# DM1098LUXD-LITE_Power_Supply.net
KiCad netlist of a schematic drawn in Altium Designer
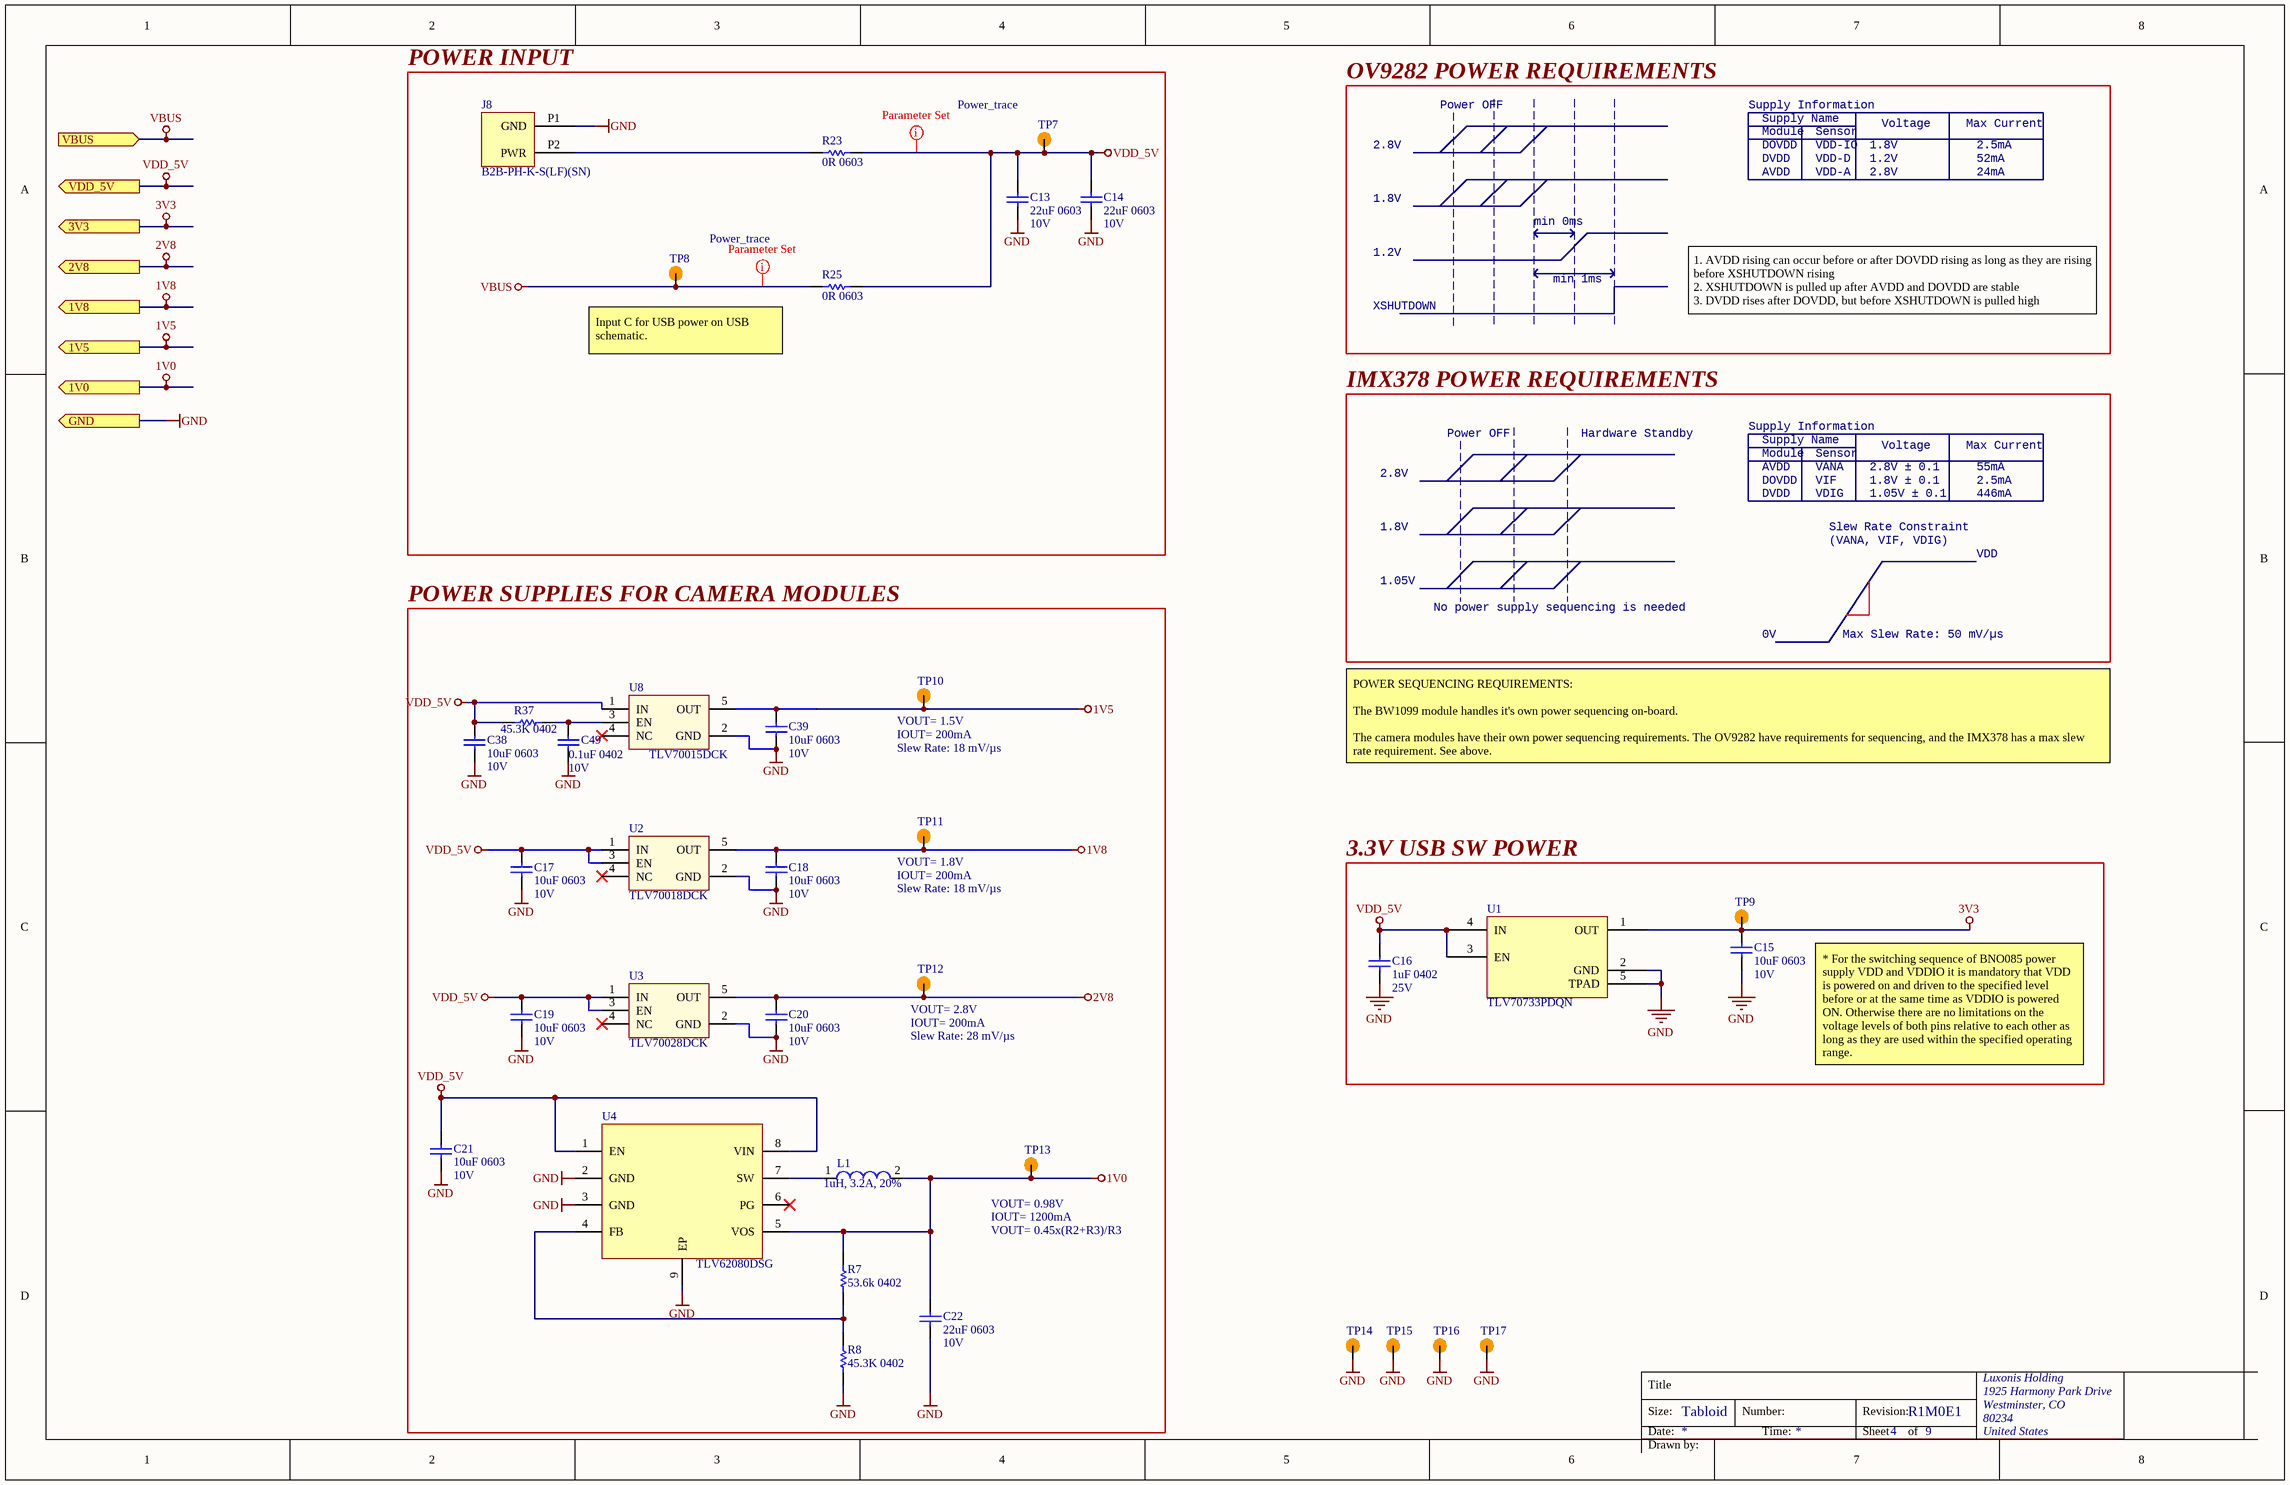
[diagram p0: DM1098LUXD-LITE_Power_Supply.SchDoc]

(export (version "E")
  (design (tool "Eeschema 10.0.6"))
  (components
    (comp (ref "C13")
      (value "22uF 0603")
      (footprint "CAP_Altium_Vault_Generic:CAPC0603(1608)100_L")
      (description "CAP CER 22UF 10V X5R 0603 20%")
      (fields (field (name "TOLERANCE") "20%") (field (name "VOLTAGE RATING") "10V"))
      (libsource (lib "LuxonisMaster") (part "GRM188R61A226ME15D"))
    )
    (comp (ref "C14")
      (value "22uF 0603")
      (footprint "CAP_Altium_Vault_Generic:CAPC0603(1608)100_L")
      (description "CAP CER 22UF 10V X5R 0603 20%")
      (fields (field (name "TOLERANCE") "20%") (field (name "VOLTAGE RATING") "10V"))
      (libsource (lib "LuxonisMaster") (part "GRM188R61A226ME15D"))
    )
    (comp (ref "C15")
      (value "10uF 0603")
      (footprint "CAP_Altium_Vault_Generic:CAPC0603(1608)100_L")
      (description "CAP CER 10UF 10V X5R 0603 20%")
      (fields (field (name "TOLERANCE") "20%") (field (name "VOLTAGE RATING") "10V"))
      (libsource (lib "LuxonisMaster") (part "GRM188R61A106ME69D"))
    )
    (comp (ref "C16")
      (value "1uF 0402")
      (footprint "CAP_Altium_Vault_Generic:CAPC0402(1005)70_L")
      (description "CAP CER 1UF 25V X5R 0402 10%")
      (fields
        (field (name "TOLERANCE") "10%")
        (field (name "VOLTAGE") "25V")
        (field (name "VOLTAGE RATING") "25V")
      )
      (libsource (lib "LuxonisMaster") (part "GRM155R61E105KA12D"))
    )
    (comp (ref "C17")
      (value "10uF 0603")
      (footprint "CAP_Altium_Vault_Generic:CAPC0603(1608)100_L")
      (description "CAP CER 10UF 10V X5R 0603 20%")
      (fields (field (name "TOLERANCE") "20%") (field (name "VOLTAGE RATING") "10V"))
      (libsource (lib "LuxonisMaster") (part "GRM188R61A106ME69D"))
    )
    (comp (ref "C18")
      (value "10uF 0603")
      (footprint "CAP_Altium_Vault_Generic:CAPC0603(1608)100_L")
      (description "CAP CER 10UF 10V X5R 0603 20%")
      (fields (field (name "TOLERANCE") "20%") (field (name "VOLTAGE RATING") "10V"))
      (libsource (lib "LuxonisMaster") (part "GRM188R61A106ME69D"))
    )
    (comp (ref "C19")
      (value "10uF 0603")
      (footprint "CAP_Altium_Vault_Generic:CAPC0603(1608)100_L")
      (description "CAP CER 10UF 10V X5R 0603 20%")
      (fields (field (name "TOLERANCE") "20%") (field (name "VOLTAGE RATING") "10V"))
      (libsource (lib "LuxonisMaster") (part "GRM188R61A106ME69D"))
    )
    (comp (ref "C20")
      (value "10uF 0603")
      (footprint "CAP_Altium_Vault_Generic:CAPC0603(1608)100_L")
      (description "CAP CER 10UF 10V X5R 0603 20%")
      (fields (field (name "TOLERANCE") "20%") (field (name "VOLTAGE RATING") "10V"))
      (libsource (lib "LuxonisMaster") (part "GRM188R61A106ME69D"))
    )
    (comp (ref "C21")
      (value "10uF 0603")
      (footprint "CAP_Altium_Vault_Generic:CAPC0603(1608)100_L")
      (description "CAP CER 10UF 10V X5R 0603 20%")
      (fields (field (name "TOLERANCE") "20%") (field (name "VOLTAGE RATING") "10V"))
      (libsource (lib "LuxonisMaster") (part "GRM188R61A106ME69D"))
    )
    (comp (ref "C22")
      (value "22uF 0603")
      (footprint "CAP_Altium_Vault_Generic:CAPC0603(1608)100_L")
      (description "CAP CER 22UF 10V X5R 0603 20%")
      (fields (field (name "TOLERANCE") "20%") (field (name "VOLTAGE RATING") "10V"))
      (libsource (lib "LuxonisMaster") (part "GRM188R61A226ME15D"))
    )
    (comp (ref "C38")
      (value "10uF 0603")
      (footprint "CAP_Altium_Vault_Generic:CAPC0603(1608)100_L")
      (description "CAP CER 10UF 10V X5R 0603 20%")
      (fields (field (name "TOLERANCE") "20%") (field (name "VOLTAGE RATING") "10V"))
      (libsource (lib "LuxonisMaster") (part "GRM188R61A106ME69D"))
    )
    (comp (ref "C39")
      (value "10uF 0603")
      (footprint "CAP_Altium_Vault_Generic:CAPC0603(1608)100_L")
      (description "CAP CER 10UF 10V X5R 0603 20%")
      (fields (field (name "TOLERANCE") "20%") (field (name "VOLTAGE RATING") "10V"))
      (libsource (lib "LuxonisMaster") (part "GRM188R61A106ME69D"))
    )
    (comp (ref "C49")
      (value "0.1uF 0402")
      (footprint "CAP_Altium_Vault_Generic:CAPC0402(1005)70_L")
      (description "CAP CER 0.1UF 10V X7R 0402 5%")
      (fields (field (name "TOLERANCE") "5%") (field (name "VOLTAGE RATING") "10V"))
      (libsource (lib "LuxonisMaster") (part "GRM155R71A104JA01D"))
    )
    (comp (ref "J8")
      (value "B2B-PH-K-S(LF)(SN)")
      (footprint "LuxonisMaster:B2B-PH-K-S(LF)(SN)")
      (description "CONN HEADER VERT 2POS 2MM")
      (libsource (lib "LuxonisMaster") (part "B2B-PH-K-S(LF)(SN)"))
    )
    (comp (ref "L1")
      (value "1uH, 3.2A, 20%")
      (footprint "LuxonisMaster:DFE252012P-1R0M=P2")
      (description "FIXED IND 1UH 3.2A 42 MOHM SMD")
      (fields
        (field (name "MANUFACTURER") "Murata")
        (field (name "MANUFACTURER PART NUMBER") "DFE252012P-1R0M=P2")
      )
      (libsource (lib "LuxonisMaster") (part "DFE252012P-1R0M=P2"))
    )
    (comp (ref "R7")
      (value "53.6k 0402")
      (footprint "RES_Altium_Vault_Generic:RESC0402(1005)_L")
      (description "RES SMD 53.6K OHM 1% 1/16W 0402")
      (fields (field (name "TOLERANCE") "1%"))
      (libsource (lib "LuxonisMaster") (part "CRCW040253K6FKED"))
    )
    (comp (ref "R8")
      (value "45.3K 0402")
      (footprint "RES_Altium_Vault_Generic:RESC0402(1005)_L")
      (description "RES SMD 45.3K OHM 1% 1/16W 0402")
      (fields (field (name "TOLERANCE") "1%"))
      (libsource (lib "LuxonisMaster") (part "RC0402FR-0745K3L"))
    )
    (comp (ref "R23")
      (value "0R 0603")
      (footprint "RES_Altium_Vault_Generic:RESC0603(1608)_N")
      (fields (field (name "TOLERANCE") "5%"))
      (libsource (lib "LuxonisMaster") (part "CRCW06030000Z0EA"))
    )
    (comp (ref "R25")
      (value "0R 0603")
      (footprint "RES_Altium_Vault_Generic:RESC0603(1608)_N")
      (fields (field (name "TOLERANCE") "5%"))
      (libsource (lib "LuxonisMaster") (part "CRCW06030000Z0EA"))
    )
    (comp (ref "R37")
      (value "45.3K 0402")
      (footprint "RES_Altium_Vault_Generic:RESC0402(1005)_L")
      (description "RES SMD 45.3K OHM 1% 1/16W 0402")
      (fields (field (name "TOLERANCE") "1%"))
      (libsource (lib "LuxonisMaster") (part "RC0402FR-0745K3L"))
    )
    (comp (ref "TP7")
      (value "TP100_200_NS")
      (footprint "LuxonisMaster:TP100_200_NS")
      (libsource (lib "LuxonisMaster") (part "TEST_POINT"))
    )
    (comp (ref "TP8")
      (value "TP100_200_NS")
      (footprint "LuxonisMaster:TP100_200_NS")
      (libsource (lib "LuxonisMaster") (part "TEST_POINT"))
    )
    (comp (ref "TP9")
      (value "TP100_200_NS")
      (footprint "LuxonisMaster:TP100_200_NS")
      (libsource (lib "LuxonisMaster") (part "TEST_POINT"))
    )
    (comp (ref "TP10")
      (value "TP100_200_NS")
      (footprint "LuxonisMaster:TP100_200_NS")
      (libsource (lib "LuxonisMaster") (part "TEST_POINT"))
    )
    (comp (ref "TP11")
      (value "TP100_200_NS")
      (footprint "LuxonisMaster:TP100_200_NS")
      (libsource (lib "LuxonisMaster") (part "TEST_POINT"))
    )
    (comp (ref "TP12")
      (value "TP100_200_NS")
      (footprint "LuxonisMaster:TP100_200_NS")
      (libsource (lib "LuxonisMaster") (part "TEST_POINT"))
    )
    (comp (ref "TP13")
      (value "TP100_200_NS")
      (footprint "LuxonisMaster:TP100_200_NS")
      (libsource (lib "LuxonisMaster") (part "TEST_POINT"))
    )
    (comp (ref "TP14")
      (value "TP100_200_NS")
      (footprint "LuxonisMaster:TP100_200_NS")
      (libsource (lib "LuxonisMaster") (part "TEST_POINT"))
    )
    (comp (ref "TP15")
      (value "TP100_200_NS")
      (footprint "LuxonisMaster:TP100_200_NS")
      (libsource (lib "LuxonisMaster") (part "TEST_POINT"))
    )
    (comp (ref "TP16")
      (value "TP100_200_NS")
      (footprint "LuxonisMaster:TP100_200_NS")
      (libsource (lib "LuxonisMaster") (part "TEST_POINT"))
    )
    (comp (ref "TP17")
      (value "TP100_200_NS")
      (footprint "LuxonisMaster:TP100_200_NS")
      (libsource (lib "LuxonisMaster") (part "TEST_POINT"))
    )
    (comp (ref "U1")
      (value "TLV70733PDQN")
      (footprint "LuxonisMaster:TLV70733PDQN")
      (description "IC REG LINEAR 3.3V 200MA 4X2SON Linear Voltage Regulator IC  1 Output  200mA 4-X2SON (1x1)")
      (libsource (lib "LuxonisMaster") (part "TLV70733PDQN"))
    )
    (comp (ref "U2")
      (value "TLV70018DCK")
      (footprint "LuxonisMaster:TLV70018DCK")
      (description "IC REG LINEAR 1.8V 200MA SC70-5 Linear Voltage Regulator IC  1 Output  200mA SC-70-5")
      (libsource (lib "LuxonisMaster") (part "TLV70018DCK"))
    )
    (comp (ref "U3")
      (value "TLV70028DCK")
      (footprint "LuxonisMaster:TLV70028DCK")
      (description "IC REG LINEAR 2.8V 200MA SC70-5 Linear Voltage Regulator IC  1 Output  200mA SC-70-5")
      (libsource (lib "LuxonisMaster") (part "TLV70028DCK"))
    )
    (comp (ref "U4")
      (value "TLV62080DSG")
      (footprint "LuxonisMaster:TLV62080DSG")
      (description "IC REG BUCK ADJ 1.2A SYNC 8WSON")
      (libsource (lib "LuxonisMaster") (part "TLV62080DSG"))
    )
    (comp (ref "U8")
      (value "TLV70015DCK")
      (footprint "LuxonisMaster:TLV70015DCK")
      (description "Fixed Positive LDO Regulator, 1.5V, PMOS, PDSO5")
      (libsource (lib "LuxonisMaster") (part "TLV70015DCK"))
    )
  )
  (nets
    (net (code "1") (name "1V0") (class "Default")
      (node (ref "C22") (pin "2") (pinfunction "2_2") (pintype "passive"))
      (node (ref "L1") (pin "2") (pinfunction "2_2") (pintype "passive"))
      (node (ref "R7") (pin "2") (pinfunction "2_2") (pintype "passive"))
      (node (ref "TP13") (pin "1") (pintype "passive"))
      (node (ref "U4") (pin "5") (pinfunction "VOS_5") (pintype "passive"))
    )
    (net (code "2") (name "1V5") (class "Default")
      (node (ref "C39") (pin "2") (pinfunction "2_2") (pintype "passive"))
      (node (ref "TP10") (pin "1") (pintype "passive"))
      (node (ref "U8") (pin "5") (pinfunction "OUT_5") (pintype "passive"))
    )
    (net (code "3") (name "1V8") (class "Default")
      (node (ref "C18") (pin "2") (pinfunction "2_2") (pintype "passive"))
      (node (ref "TP11") (pin "1") (pintype "passive"))
      (node (ref "U2") (pin "5") (pinfunction "OUT_5") (pintype "passive"))
    )
    (net (code "4") (name "2V8") (class "Default")
      (node (ref "C20") (pin "2") (pinfunction "2_2") (pintype "passive"))
      (node (ref "TP12") (pin "1") (pintype "passive"))
      (node (ref "U3") (pin "5") (pinfunction "OUT_5") (pintype "passive"))
    )
    (net (code "5") (name "3V3") (class "Default")
      (node (ref "C15") (pin "2") (pinfunction "2_2") (pintype "passive"))
      (node (ref "TP9") (pin "1") (pintype "passive"))
      (node (ref "U1") (pin "1") (pinfunction "OUT_1") (pintype "power_in"))
    )
    (net (code "6") (name "GND") (class "Default")
      (node (ref "C13") (pin "1") (pinfunction "1_1") (pintype "passive"))
      (node (ref "C14") (pin "1") (pinfunction "1_1") (pintype "passive"))
      (node (ref "C15") (pin "1") (pinfunction "1_1") (pintype "passive"))
      (node (ref "C16") (pin "1") (pinfunction "1_1") (pintype "passive"))
      (node (ref "C17") (pin "1") (pinfunction "1_1") (pintype "passive"))
      (node (ref "C18") (pin "1") (pinfunction "1_1") (pintype "passive"))
      (node (ref "C19") (pin "1") (pinfunction "1_1") (pintype "passive"))
      (node (ref "C20") (pin "1") (pinfunction "1_1") (pintype "passive"))
      (node (ref "C21") (pin "1") (pinfunction "1_1") (pintype "passive"))
      (node (ref "C22") (pin "1") (pinfunction "1_1") (pintype "passive"))
      (node (ref "C38") (pin "1") (pinfunction "1_1") (pintype "passive"))
      (node (ref "C39") (pin "1") (pinfunction "1_1") (pintype "passive"))
      (node (ref "C49") (pin "1") (pinfunction "1_1") (pintype "passive"))
      (node (ref "J8") (pin "P1") (pinfunction "GND_P1") (pintype "passive"))
      (node (ref "R8") (pin "1") (pinfunction "1_1") (pintype "passive"))
      (node (ref "TP14") (pin "1") (pintype "passive"))
      (node (ref "TP15") (pin "1") (pintype "passive"))
      (node (ref "TP16") (pin "1") (pintype "passive"))
      (node (ref "TP17") (pin "1") (pintype "passive"))
      (node (ref "U1") (pin "2") (pinfunction "GND_2") (pintype "power_in"))
      (node (ref "U1") (pin "5") (pinfunction "TPAD_5") (pintype "passive"))
      (node (ref "U2") (pin "2") (pinfunction "GND_2") (pintype "passive"))
      (node (ref "U3") (pin "2") (pinfunction "GND_2") (pintype "passive"))
      (node (ref "U4") (pin "2") (pinfunction "GND_2") (pintype "passive"))
      (node (ref "U4") (pin "3") (pinfunction "GND_3") (pintype "passive"))
      (node (ref "U4") (pin "9") (pinfunction "EP_9") (pintype "passive"))
      (node (ref "U8") (pin "2") (pinfunction "GND_2") (pintype "passive"))
    )
    (net (code "7") (name "Net-(J8-PWR)") (class "Default")
      (node (ref "J8") (pin "P2") (pinfunction "PWR_P2") (pintype "passive"))
      (node (ref "R23") (pin "1") (pinfunction "1_1") (pintype "passive"))
    )
    (net (code "8") (name "Net-(U4-FB)") (class "Default")
      (node (ref "R7") (pin "1") (pinfunction "1_1") (pintype "passive"))
      (node (ref "R8") (pin "2") (pinfunction "2_2") (pintype "passive"))
      (node (ref "U4") (pin "4") (pinfunction "FB_4") (pintype "passive"))
    )
    (net (code "9") (name "Net-(U4-SW)") (class "Default")
      (node (ref "L1") (pin "1") (pinfunction "1_1") (pintype "passive"))
      (node (ref "U4") (pin "7") (pinfunction "SW_7") (pintype "passive"))
    )
    (net (code "10") (name "Net-(U8-EN)") (class "Default")
      (node (ref "C49") (pin "2") (pinfunction "2_2") (pintype "passive"))
      (node (ref "R37") (pin "1") (pinfunction "1_1") (pintype "passive"))
      (node (ref "U8") (pin "3") (pinfunction "EN_3") (pintype "passive"))
    )
    (net (code "11") (name "VBUS") (class "Default")
      (node (ref "R25") (pin "1") (pinfunction "1_1") (pintype "passive"))
      (node (ref "TP8") (pin "1") (pintype "passive"))
    )
    (net (code "12") (name "VDD_5V") (class "Default")
      (node (ref "C13") (pin "2") (pinfunction "2_2") (pintype "passive"))
      (node (ref "C14") (pin "2") (pinfunction "2_2") (pintype "passive"))
      (node (ref "C16") (pin "2") (pinfunction "2_2") (pintype "passive"))
      (node (ref "C17") (pin "2") (pinfunction "2_2") (pintype "passive"))
      (node (ref "C19") (pin "2") (pinfunction "2_2") (pintype "passive"))
      (node (ref "C21") (pin "2") (pinfunction "2_2") (pintype "passive"))
      (node (ref "C38") (pin "2") (pinfunction "2_2") (pintype "passive"))
      (node (ref "R23") (pin "2") (pinfunction "2_2") (pintype "passive"))
      (node (ref "R25") (pin "2") (pinfunction "2_2") (pintype "passive"))
      (node (ref "R37") (pin "2") (pinfunction "2_2") (pintype "passive"))
      (node (ref "TP7") (pin "1") (pintype "passive"))
      (node (ref "U1") (pin "3") (pinfunction "EN_3") (pintype "power_in"))
      (node (ref "U1") (pin "4") (pinfunction "IN_4") (pintype "power_in"))
      (node (ref "U2") (pin "1") (pinfunction "IN_1") (pintype "passive"))
      (node (ref "U2") (pin "3") (pinfunction "EN_3") (pintype "passive"))
      (node (ref "U3") (pin "1") (pinfunction "IN_1") (pintype "passive"))
      (node (ref "U3") (pin "3") (pinfunction "EN_3") (pintype "passive"))
      (node (ref "U4") (pin "1") (pinfunction "EN_1") (pintype "passive"))
      (node (ref "U4") (pin "8") (pinfunction "VIN_8") (pintype "passive"))
      (node (ref "U8") (pin "1") (pinfunction "IN_1") (pintype "passive"))
    )
    (net (code "13") (name "unconnected-(U2-NC-Pad4)") (class "Default")
      (node (ref "U2") (pin "4") (pinfunction "NC_4") (pintype "passive+no_connect"))
    )
    (net (code "14") (name "unconnected-(U3-NC-Pad4)") (class "Default")
      (node (ref "U3") (pin "4") (pinfunction "NC_4") (pintype "passive+no_connect"))
    )
    (net (code "15") (name "unconnected-(U4-PG-Pad6)") (class "Default")
      (node (ref "U4") (pin "6") (pinfunction "PG_6") (pintype "passive+no_connect"))
    )
    (net (code "16") (name "unconnected-(U8-NC-Pad4)") (class "Default")
      (node (ref "U8") (pin "4") (pinfunction "NC_4") (pintype "passive+no_connect"))
    )
  )
)
